# BOOST.net
KiCad netlist of a schematic drawn in Altium Designer
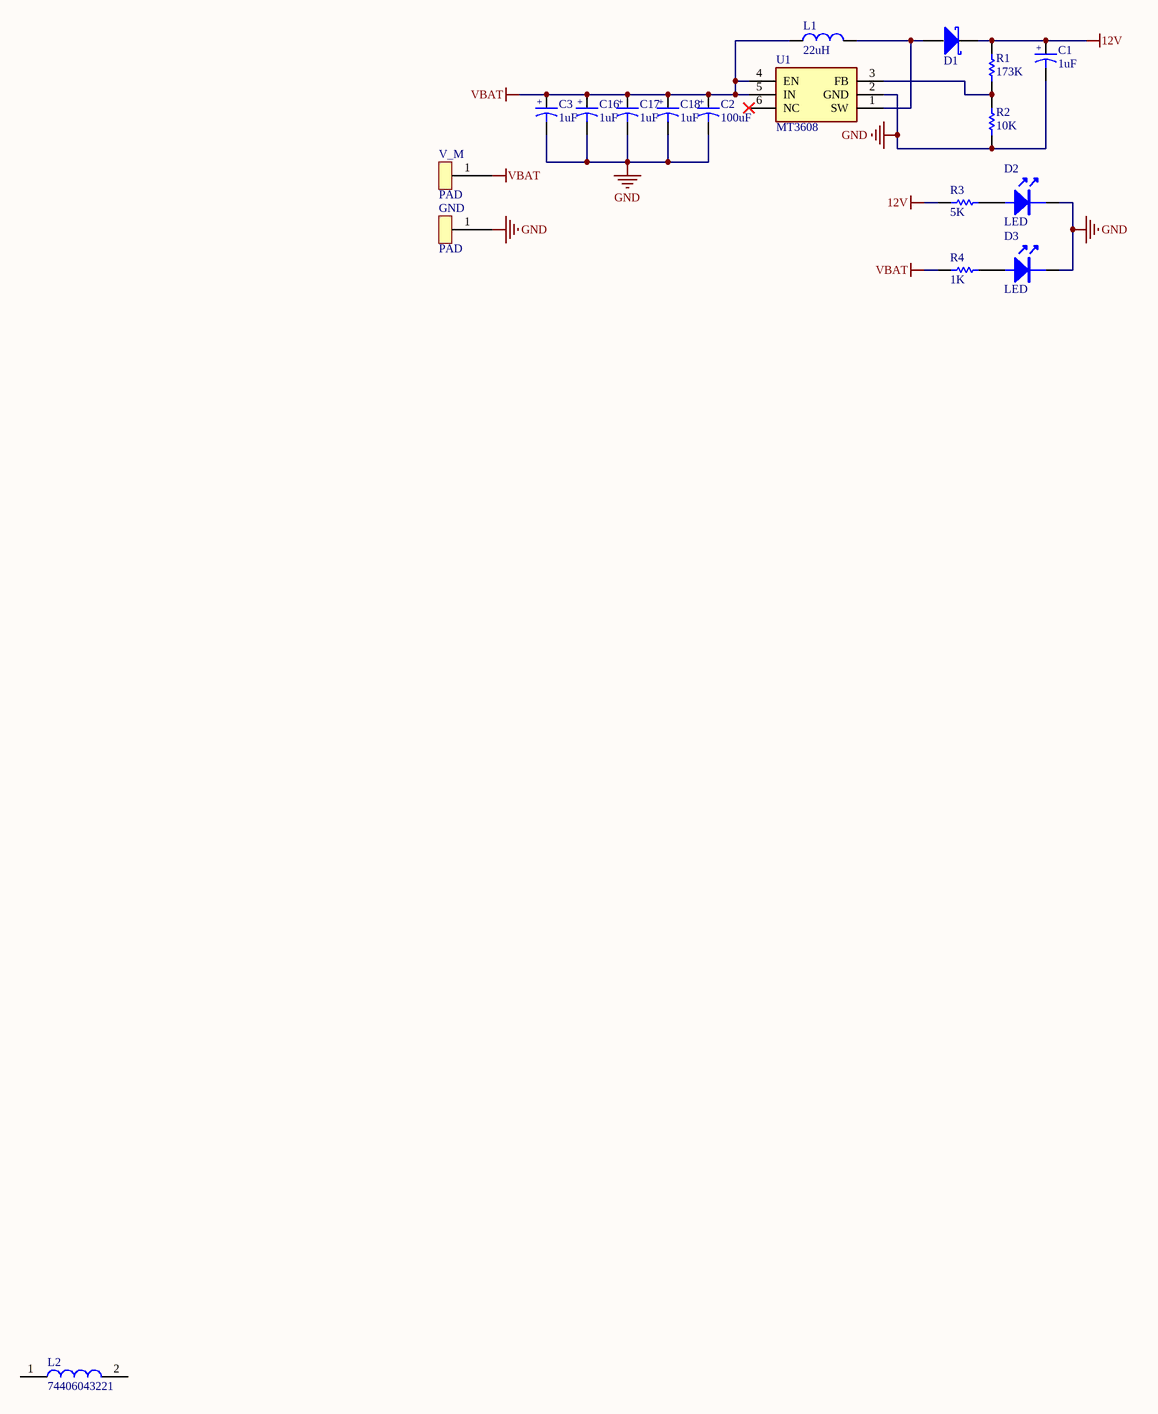
[diagram p0: BOOST.SchDoc]

(export (version "E")
  (design (tool "Eeschema 10.0.6"))
  (components
    (comp (ref "C1") (value "1uF") (footprint "C5X5") (libsource (lib "My Footprint") (part "CAP1")))
    (comp (ref "C2") (value "100uF") (footprint "C10X10") (libsource (lib "PCB_Project1") (part "Cap_polar")))
    (comp (ref "C3") (value "1uF") (footprint "C5X5") (libsource (lib "My Footprint") (part "CAP1")))
    (comp (ref "C16") (value "1uF") (footprint "C5X5") (libsource (lib "My Footprint") (part "CAP1")))
    (comp (ref "C17") (value "1uF") (footprint "C5X5") (libsource (lib "My Footprint") (part "CAP1")))
    (comp (ref "C18") (value "1uF") (footprint "C5X5") (libsource (lib "My Footprint") (part "CAP1")))
    (comp (ref "D1")
      (value "Diode Schottky")
      (footprint "DO-214AC")
      (libsource (lib "通用驱动") (part "Diode Schottky"))
    )
    (comp (ref "D2")
      (value "LED")
      (footprint "0603_LED")
      (description "LED 发光二极管")
      (libsource (lib "My Footprint") (part "LED"))
    )
    (comp (ref "D3")
      (value "LED")
      (footprint "0603_LED")
      (description "LED 发光二极管")
      (libsource (lib "My Footprint") (part "LED"))
    )
    (comp (ref "GND") (value "PAD") (footprint "PAD") (libsource (lib "My Footprint") (part "PAD")))
    (comp (ref "L1")
      (value "22uH")
      (footprint "L 5x5")
      (libsource (lib "My Footprint") (part "L_Inductance"))
    )
    (comp (ref "L2")
      (value "74406043221")
      (footprint "PcbLib_Online:INDPM4848X280N")
      (description "Inductor")
      (fields (field (name "MOUSER PART NUMBER") "710-74406043221") (field (name "RS PART NUMBER") "1354936"))
      (libsource (lib "*") (part "74406043221"))
    )
    (comp (ref "R1")
      (value "173K")
      (footprint "0603_R")
      (description "Resistor")
      (fields (field (name "PUBLISHER") "Altium Limited"))
      (libsource (lib "My Footprint") (part "RES"))
    )
    (comp (ref "R2")
      (value "10K")
      (footprint "0603_R")
      (description "Resistor")
      (fields (field (name "PUBLISHER") "Altium Limited"))
      (libsource (lib "My Footprint") (part "RES"))
    )
    (comp (ref "R3")
      (value "5K")
      (footprint "0603_R")
      (description "Resistor")
      (fields (field (name "PUBLISHER") "Altium Limited"))
      (libsource (lib "My Footprint") (part "RES"))
    )
    (comp (ref "R4")
      (value "1K")
      (footprint "0603_R")
      (description "Resistor")
      (fields (field (name "PUBLISHER") "Altium Limited"))
      (libsource (lib "My Footprint") (part "RES"))
    )
    (comp (ref "U1")
      (value "MT3608")
      (footprint "PcbLib_Online:SOT95P280X145-6N")
      (description "Undefined or Miscellaneous")
      (libsource (lib "sch_online") (part "MT3608"))
    )
    (comp (ref "V_M") (value "PAD") (footprint "PAD") (libsource (lib "My Footprint") (part "PAD")))
  )
  (nets
    (net (code "1") (name "12V") (class "Default")
      (node (ref "C1") (pin "1") (pinfunction "1_1") (pintype "passive"))
      (node (ref "D1") (pin "2") (pinfunction "K_2") (pintype "passive"))
      (node (ref "R1") (pin "2") (pinfunction "2_2") (pintype "passive"))
      (node (ref "R3") (pin "2") (pinfunction "2_2") (pintype "passive"))
    )
    (net (code "2") (name "GND") (class "Default")
      (node (ref "C1") (pin "2") (pinfunction "2_2") (pintype "passive"))
      (node (ref "C16") (pin "2") (pinfunction "2_2") (pintype "passive"))
      (node (ref "C17") (pin "2") (pinfunction "2_2") (pintype "passive"))
      (node (ref "C18") (pin "2") (pinfunction "2_2") (pintype "passive"))
      (node (ref "C2") (pin "2") (pinfunction "2_2") (pintype "passive"))
      (node (ref "C3") (pin "2") (pinfunction "2_2") (pintype "passive"))
      (node (ref "D2") (pin "2") (pinfunction "K_2") (pintype "passive"))
      (node (ref "D3") (pin "2") (pinfunction "K_2") (pintype "passive"))
      (node (ref "GND") (pin "1") (pintype "passive"))
      (node (ref "R2") (pin "1") (pinfunction "1_1") (pintype "passive"))
      (node (ref "U1") (pin "2") (pinfunction "GND_2") (pintype "passive"))
    )
    (net (code "3") (name "Net-(D1-A)") (class "Default")
      (node (ref "D1") (pin "1") (pinfunction "A_1") (pintype "passive"))
      (node (ref "L1") (pin "2") (pinfunction "2_2") (pintype "passive"))
      (node (ref "U1") (pin "1") (pinfunction "SW_1") (pintype "passive"))
    )
    (net (code "4") (name "Net-(D2-A)") (class "Default")
      (node (ref "D2") (pin "1") (pinfunction "A_1") (pintype "passive"))
      (node (ref "R3") (pin "1") (pinfunction "1_1") (pintype "passive"))
    )
    (net (code "5") (name "Net-(D3-A)") (class "Default")
      (node (ref "D3") (pin "1") (pinfunction "A_1") (pintype "passive"))
      (node (ref "R4") (pin "1") (pinfunction "1_1") (pintype "passive"))
    )
    (net (code "6") (name "Net-(U1-FB)") (class "Default")
      (node (ref "R1") (pin "1") (pinfunction "1_1") (pintype "passive"))
      (node (ref "R2") (pin "2") (pinfunction "2_2") (pintype "passive"))
      (node (ref "U1") (pin "3") (pinfunction "FB_3") (pintype "passive"))
    )
    (net (code "7") (name "VBAT") (class "Default")
      (node (ref "C16") (pin "1") (pinfunction "1_1") (pintype "passive"))
      (node (ref "C17") (pin "1") (pinfunction "1_1") (pintype "passive"))
      (node (ref "C18") (pin "1") (pinfunction "1_1") (pintype "passive"))
      (node (ref "C2") (pin "1") (pinfunction "1_1") (pintype "passive"))
      (node (ref "C3") (pin "1") (pinfunction "1_1") (pintype "passive"))
      (node (ref "L1") (pin "1") (pinfunction "1_1") (pintype "passive"))
      (node (ref "R4") (pin "2") (pinfunction "2_2") (pintype "passive"))
      (node (ref "U1") (pin "4") (pinfunction "EN_4") (pintype "passive"))
      (node (ref "U1") (pin "5") (pinfunction "IN_5") (pintype "passive"))
      (node (ref "V_M") (pin "1") (pintype "passive"))
    )
    (net (code "8") (name "unconnected-(L2-Pad1)") (class "Default")
      (node (ref "L2") (pin "1") (pinfunction "1_1") (pintype "passive"))
    )
    (net (code "9") (name "unconnected-(L2-Pad2)") (class "Default")
      (node (ref "L2") (pin "2") (pinfunction "2_2") (pintype "passive"))
    )
    (net (code "10") (name "unconnected-(U1-NC-Pad6)") (class "Default")
      (node (ref "U1") (pin "6") (pinfunction "NC_6") (pintype "passive+no_connect"))
    )
  )
)
